# 7_seg_display.net
KiCad netlist of a schematic drawn in Altium Designer
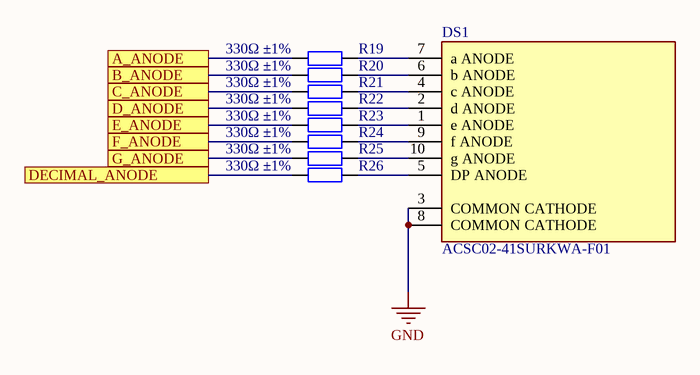
[diagram p0: 7_seg_display.SchDoc]

(export (version "E")
  (design (tool "Eeschema 10.0.6"))
  (components
    (comp (ref "DS1")
      (value "ACSC02-41SURKWA-F01")
      (footprint "FP-ACSC02-41SURKWA-F01-MFG")
      (description "DISPLAY 7-SEG 0.2\" SGL RED 10SMD")
      (libsource (lib "Altium Content Vault") (part "0e920bf6b93db43d611184977c40d65"))
    )
    (comp (ref "R19")
      (value "330Ω ±1%")
      (footprint "0603_R")
      (description "Chip resistor")
      (fields (field (name "MANUFACTURER") "Uniroyal Elec") (field (name "PARTNUMBER") "0603WAF3300T5E"))
      (libsource (lib "RES") (part "0603 330R (3300) 1%"))
    )
    (comp (ref "R20")
      (value "330Ω ±1%")
      (footprint "0603_R")
      (description "Chip resistor")
      (fields (field (name "MANUFACTURER") "Uniroyal Elec") (field (name "PARTNUMBER") "0603WAF3300T5E"))
      (libsource (lib "RES") (part "0603 330R (3300) 1%"))
    )
    (comp (ref "R21")
      (value "330Ω ±1%")
      (footprint "0603_R")
      (description "Chip resistor")
      (fields (field (name "MANUFACTURER") "Uniroyal Elec") (field (name "PARTNUMBER") "0603WAF3300T5E"))
      (libsource (lib "RES") (part "0603 330R (3300) 1%"))
    )
    (comp (ref "R22")
      (value "330Ω ±1%")
      (footprint "0603_R")
      (description "Chip resistor")
      (fields (field (name "MANUFACTURER") "Uniroyal Elec") (field (name "PARTNUMBER") "0603WAF3300T5E"))
      (libsource (lib "RES") (part "0603 330R (3300) 1%"))
    )
    (comp (ref "R23")
      (value "330Ω ±1%")
      (footprint "0603_R")
      (description "Chip resistor")
      (fields (field (name "MANUFACTURER") "Uniroyal Elec") (field (name "PARTNUMBER") "0603WAF3300T5E"))
      (libsource (lib "RES") (part "0603 330R (3300) 1%"))
    )
    (comp (ref "R24")
      (value "330Ω ±1%")
      (footprint "0603_R")
      (description "Chip resistor")
      (fields (field (name "MANUFACTURER") "Uniroyal Elec") (field (name "PARTNUMBER") "0603WAF3300T5E"))
      (libsource (lib "RES") (part "0603 330R (3300) 1%"))
    )
    (comp (ref "R25")
      (value "330Ω ±1%")
      (footprint "0603_R")
      (description "Chip resistor")
      (fields (field (name "MANUFACTURER") "Uniroyal Elec") (field (name "PARTNUMBER") "0603WAF3300T5E"))
      (libsource (lib "RES") (part "0603 330R (3300) 1%"))
    )
    (comp (ref "R26")
      (value "330Ω ±1%")
      (footprint "0603_R")
      (description "Chip resistor")
      (fields (field (name "MANUFACTURER") "Uniroyal Elec") (field (name "PARTNUMBER") "0603WAF3300T5E"))
      (libsource (lib "RES") (part "0603 330R (3300) 1%"))
    )
  )
  (nets
    (net (code "1") (name "/A_ANODE") (class "Default")
      (node (ref "R19") (pin "2") (pinfunction "2_2") (pintype "passive"))
    )
    (net (code "2") (name "/B_ANODE") (class "Default")
      (node (ref "R20") (pin "2") (pinfunction "2_2") (pintype "passive"))
    )
    (net (code "3") (name "/C_ANODE") (class "Default")
      (node (ref "R21") (pin "2") (pinfunction "2_2") (pintype "passive"))
    )
    (net (code "4") (name "/DECIMAL_ANODE") (class "Default")
      (node (ref "R26") (pin "2") (pinfunction "2_2") (pintype "passive"))
    )
    (net (code "5") (name "/D_ANODE") (class "Default")
      (node (ref "R22") (pin "2") (pinfunction "2_2") (pintype "passive"))
    )
    (net (code "6") (name "/E_ANODE") (class "Default")
      (node (ref "R23") (pin "2") (pinfunction "2_2") (pintype "passive"))
    )
    (net (code "7") (name "/F_ANODE") (class "Default")
      (node (ref "R24") (pin "2") (pinfunction "2_2") (pintype "passive"))
    )
    (net (code "8") (name "/G_ANODE") (class "Default")
      (node (ref "R25") (pin "2") (pinfunction "2_2") (pintype "passive"))
    )
    (net (code "9") (name "GND") (class "Default")
      (node (ref "DS1") (pin "3") (pinfunction "COMMON_CATHODE_3") (pintype "passive"))
      (node (ref "DS1") (pin "8") (pinfunction "COMMON_CATHODE_8") (pintype "passive"))
    )
    (net (code "10") (name "Net-(DS1-DP_ANODE)") (class "Default")
      (node (ref "DS1") (pin "5") (pinfunction "DP_ANODE_5") (pintype "passive"))
      (node (ref "R26") (pin "1") (pinfunction "1_1") (pintype "passive"))
    )
    (net (code "11") (name "Net-(DS1-a_ANODE)") (class "Default")
      (node (ref "DS1") (pin "7") (pinfunction "a_ANODE_7") (pintype "passive"))
      (node (ref "R19") (pin "1") (pinfunction "1_1") (pintype "passive"))
    )
    (net (code "12") (name "Net-(DS1-b_ANODE)") (class "Default")
      (node (ref "DS1") (pin "6") (pinfunction "b_ANODE_6") (pintype "passive"))
      (node (ref "R20") (pin "1") (pinfunction "1_1") (pintype "passive"))
    )
    (net (code "13") (name "Net-(DS1-c_ANODE)") (class "Default")
      (node (ref "DS1") (pin "4") (pinfunction "c_ANODE_4") (pintype "passive"))
      (node (ref "R21") (pin "1") (pinfunction "1_1") (pintype "passive"))
    )
    (net (code "14") (name "Net-(DS1-d_ANODE)") (class "Default")
      (node (ref "DS1") (pin "2") (pinfunction "d_ANODE_2") (pintype "passive"))
      (node (ref "R22") (pin "1") (pinfunction "1_1") (pintype "passive"))
    )
    (net (code "15") (name "Net-(DS1-e_ANODE)") (class "Default")
      (node (ref "DS1") (pin "1") (pinfunction "e_ANODE_1") (pintype "passive"))
      (node (ref "R23") (pin "1") (pinfunction "1_1") (pintype "passive"))
    )
    (net (code "16") (name "Net-(DS1-f_ANODE)") (class "Default")
      (node (ref "DS1") (pin "9") (pinfunction "f_ANODE_9") (pintype "passive"))
      (node (ref "R24") (pin "1") (pinfunction "1_1") (pintype "passive"))
    )
    (net (code "17") (name "Net-(DS1-g_ANODE)") (class "Default")
      (node (ref "DS1") (pin "10") (pinfunction "g_ANODE_10") (pintype "passive"))
      (node (ref "R25") (pin "1") (pinfunction "1_1") (pintype "passive"))
    )
  )
)
